# CLKB_RS232_port.net
KiCad netlist of a schematic drawn in Altium Designer
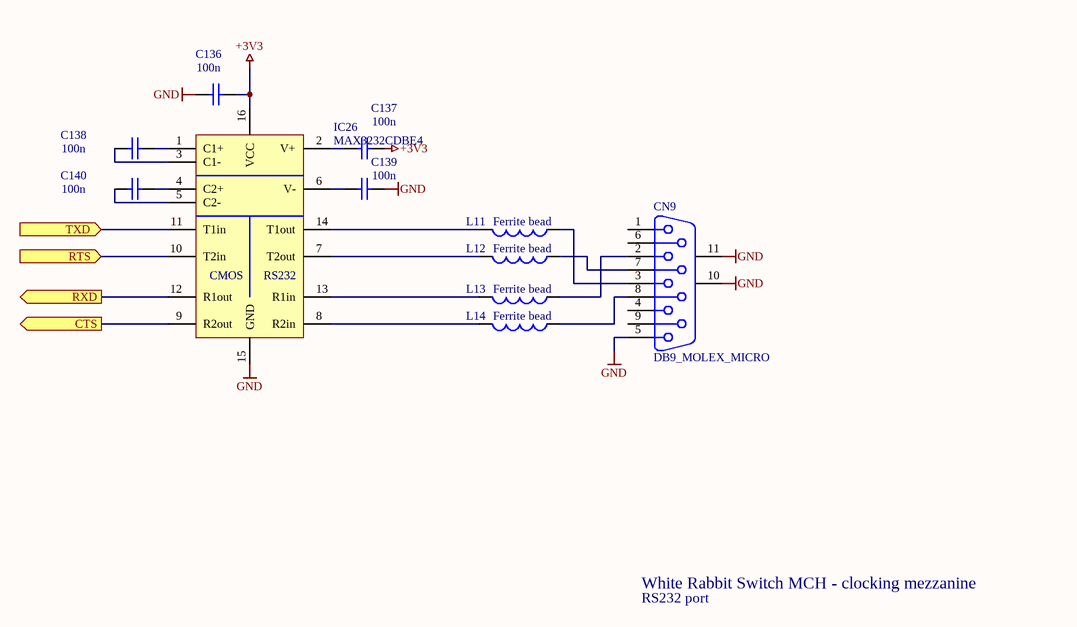
[diagram p0: CLKB_RS232_port.SchDoc]

(export (version "E")
  (design (tool "Eeschema 10.0.6"))
  (components
    (comp (ref "C136")
      (value "100n")
      (footprint "CAPC1608X87N")
      (description "Non-polarised capacitor")
      (fields
        (field (name "PART NUMBER") "CC0603_100NF_50V_10%_X7R")
        (field (name "VOLTAGE") "50V")
        (field (name "AUTHOR") "CERN DEM JLC")
      )
      (libsource (lib "Capacitors") (part "Capacitor - non polarized"))
    )
    (comp (ref "C137")
      (value "100n")
      (footprint "CAPC1608X87N")
      (description "Non-polarised capacitor")
      (fields
        (field (name "PART NUMBER") "CC0603_100NF_50V_10%_X7R")
        (field (name "VOLTAGE") "50V")
        (field (name "AUTHOR") "CERN DEM JLC")
      )
      (libsource (lib "Capacitors") (part "Capacitor - non polarized"))
    )
    (comp (ref "C138")
      (value "100n")
      (footprint "CAPC1608X87N")
      (description "Non-polarised capacitor")
      (fields
        (field (name "PART NUMBER") "CC0603_100NF_50V_10%_X7R")
        (field (name "VOLTAGE") "50V")
        (field (name "AUTHOR") "CERN DEM JLC")
      )
      (libsource (lib "Capacitors") (part "Capacitor - non polarized"))
    )
    (comp (ref "C139")
      (value "100n")
      (footprint "CAPC1608X87N")
      (description "Non-polarised capacitor")
      (fields
        (field (name "PART NUMBER") "CC0603_100NF_50V_10%_X7R")
        (field (name "VOLTAGE") "50V")
        (field (name "AUTHOR") "CERN DEM JLC")
      )
      (libsource (lib "Capacitors") (part "Capacitor - non polarized"))
    )
    (comp (ref "C140")
      (value "100n")
      (footprint "CAPC1608X87N")
      (description "Non-polarised capacitor")
      (fields
        (field (name "PART NUMBER") "CC0603_100NF_50V_10%_X7R")
        (field (name "VOLTAGE") "50V")
        (field (name "AUTHOR") "CERN DEM JLC")
      )
      (libsource (lib "Capacitors") (part "Capacitor - non polarized"))
    )
    (comp (ref "CN9")
      (value "DB9_MOLEX_MICRO")
      (footprint "DSUB_MINI_9")
      (description "Receptacle Assembly, 9 Position, Right Angle")
      (fields (field (name "MANUFACTURER") "Generic Components") (field (name "PUBLISHER") "Altium Limited"))
      (libsource (lib "wr_switch") (part "CON_DB9_H"))
    )
    (comp (ref "IC26")
      (value "MAX3232CDBE4")
      (footprint "Miscellaneous Devices:SSOP16")
      (libsource (lib "wr_switch") (part "IFC_MAX3232"))
    )
    (comp (ref "L11")
      (value "Ferrite bead")
      (footprint "L0603")
      (fields (field (name "PUBLISHER") "Altium Limited"))
      (libsource (lib "Miscellaneous Devices") (part "Inductor"))
    )
    (comp (ref "L12")
      (value "Ferrite bead")
      (footprint "L0603")
      (fields (field (name "PUBLISHER") "Altium Limited"))
      (libsource (lib "Miscellaneous Devices") (part "Inductor"))
    )
    (comp (ref "L13")
      (value "Ferrite bead")
      (footprint "L0603")
      (fields (field (name "PUBLISHER") "Altium Limited"))
      (libsource (lib "Miscellaneous Devices") (part "Inductor"))
    )
    (comp (ref "L14")
      (value "Ferrite bead")
      (footprint "L0603")
      (fields (field (name "PUBLISHER") "Altium Limited"))
      (libsource (lib "Miscellaneous Devices") (part "Inductor"))
    )
  )
  (nets
    (net (code "1") (name "+3V3") (class "Default")
      (node (ref "C136") (pin "2") (pinfunction "2_2") (pintype "passive"))
      (node (ref "C137") (pin "2") (pinfunction "2_2") (pintype "passive"))
      (node (ref "IC26") (pin "16") (pinfunction "VCC_16") (pintype "passive"))
    )
    (net (code "2") (name "/CTS") (class "Default")
      (node (ref "IC26") (pin "9") (pinfunction "R2out_9") (pintype "passive"))
    )
    (net (code "3") (name "/RTS") (class "Default")
      (node (ref "IC26") (pin "10") (pinfunction "T2in_10") (pintype "passive"))
    )
    (net (code "4") (name "/RXD") (class "Default")
      (node (ref "IC26") (pin "12") (pinfunction "R1out_12") (pintype "passive"))
    )
    (net (code "5") (name "/TXD") (class "Default")
      (node (ref "IC26") (pin "11") (pinfunction "T1in_11") (pintype "passive"))
    )
    (net (code "6") (name "GND") (class "Default")
      (node (ref "C136") (pin "1") (pinfunction "1_1") (pintype "passive"))
      (node (ref "C139") (pin "2") (pinfunction "2_2") (pintype "passive"))
      (node (ref "CN9") (pin "10") (pinfunction "MH1_10") (pintype "passive"))
      (node (ref "CN9") (pin "11") (pinfunction "MH2_11") (pintype "passive"))
      (node (ref "CN9") (pin "5") (pinfunction "5_5") (pintype "passive"))
      (node (ref "IC26") (pin "15") (pinfunction "GND_15") (pintype "passive"))
    )
    (net (code "7") (name "Net-(CN9-Pad2)") (class "Default")
      (node (ref "CN9") (pin "2") (pinfunction "2_2") (pintype "passive"))
      (node (ref "L13") (pin "1") (pinfunction "1_1") (pintype "passive"))
    )
    (net (code "8") (name "Net-(CN9-Pad3)") (class "Default")
      (node (ref "CN9") (pin "3") (pinfunction "3_3") (pintype "passive"))
      (node (ref "L11") (pin "1") (pinfunction "1_1") (pintype "passive"))
    )
    (net (code "9") (name "Net-(CN9-Pad7)") (class "Default")
      (node (ref "CN9") (pin "7") (pinfunction "7_7") (pintype "passive"))
      (node (ref "L12") (pin "1") (pinfunction "1_1") (pintype "passive"))
    )
    (net (code "10") (name "Net-(CN9-Pad8)") (class "Default")
      (node (ref "CN9") (pin "8") (pinfunction "8_8") (pintype "passive"))
      (node (ref "L14") (pin "1") (pinfunction "1_1") (pintype "passive"))
    )
    (net (code "11") (name "Net-(IC26-C1+)") (class "Default")
      (node (ref "C138") (pin "2") (pinfunction "2_2") (pintype "passive"))
      (node (ref "IC26") (pin "1") (pinfunction "C1+_1") (pintype "passive"))
    )
    (net (code "12") (name "Net-(IC26-C1-)") (class "Default")
      (node (ref "C138") (pin "1") (pinfunction "1_1") (pintype "passive"))
      (node (ref "IC26") (pin "3") (pinfunction "C1-_3") (pintype "passive"))
    )
    (net (code "13") (name "Net-(IC26-C2+)") (class "Default")
      (node (ref "C140") (pin "2") (pinfunction "2_2") (pintype "passive"))
      (node (ref "IC26") (pin "4") (pinfunction "C2+_4") (pintype "passive"))
    )
    (net (code "14") (name "Net-(IC26-C2-)") (class "Default")
      (node (ref "C140") (pin "1") (pinfunction "1_1") (pintype "passive"))
      (node (ref "IC26") (pin "5") (pinfunction "C2-_5") (pintype "passive"))
    )
    (net (code "15") (name "Net-(IC26-R1in)") (class "Default")
      (node (ref "IC26") (pin "13") (pinfunction "R1in_13") (pintype "passive"))
      (node (ref "L13") (pin "2") (pinfunction "2_2") (pintype "passive"))
    )
    (net (code "16") (name "Net-(IC26-R2in)") (class "Default")
      (node (ref "IC26") (pin "8") (pinfunction "R2in_8") (pintype "passive"))
      (node (ref "L14") (pin "2") (pinfunction "2_2") (pintype "passive"))
    )
    (net (code "17") (name "Net-(IC26-T1out)") (class "Default")
      (node (ref "IC26") (pin "14") (pinfunction "T1out_14") (pintype "passive"))
      (node (ref "L11") (pin "2") (pinfunction "2_2") (pintype "passive"))
    )
    (net (code "18") (name "Net-(IC26-T2out)") (class "Default")
      (node (ref "IC26") (pin "7") (pinfunction "T2out_7") (pintype "passive"))
      (node (ref "L12") (pin "2") (pinfunction "2_2") (pintype "passive"))
    )
    (net (code "19") (name "Net-(IC26-V+)") (class "Default")
      (node (ref "C137") (pin "1") (pinfunction "1_1") (pintype "passive"))
      (node (ref "IC26") (pin "2") (pinfunction "V+_2") (pintype "passive"))
    )
    (net (code "20") (name "Net-(IC26-V-)") (class "Default")
      (node (ref "C139") (pin "1") (pinfunction "1_1") (pintype "passive"))
      (node (ref "IC26") (pin "6") (pinfunction "V-_6") (pintype "passive"))
    )
    (net (code "21") (name "unconnected-(CN9-Pad1)") (class "Default")
      (node (ref "CN9") (pin "1") (pinfunction "1_1") (pintype "passive"))
    )
    (net (code "22") (name "unconnected-(CN9-Pad4)") (class "Default")
      (node (ref "CN9") (pin "4") (pinfunction "4_4") (pintype "passive"))
    )
    (net (code "23") (name "unconnected-(CN9-Pad6)") (class "Default")
      (node (ref "CN9") (pin "6") (pinfunction "6_6") (pintype "passive"))
    )
    (net (code "24") (name "unconnected-(CN9-Pad9)") (class "Default")
      (node (ref "CN9") (pin "9") (pinfunction "9_9") (pintype "passive"))
    )
  )
)
